# EMP2.net
KiCad netlist of a schematic drawn in EAGLE
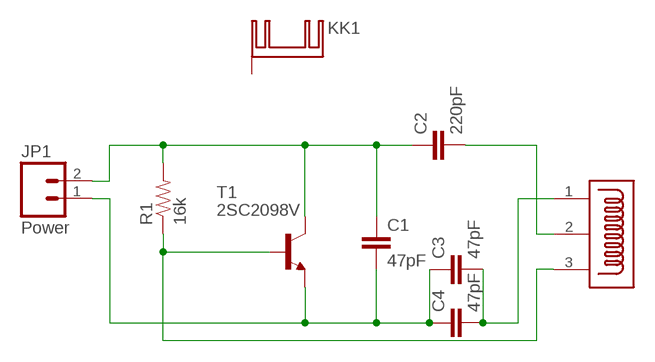
[diagram p0: schematic, sheet 1]

(export (version "E")
  (design (tool "Eeschema 10.0.6"))
  (components
    (comp (ref "C1")
      (value "47pF")
      (footprint "eagle-import:CAP-PTH-SMALL")
      (libsource (lib "eagle-import") (part "CAPPTH"))
    )
    (comp (ref "C2")
      (value "220pF")
      (footprint "eagle-import:CAP-PTH-SMALL")
      (libsource (lib "eagle-import") (part "CAPPTH"))
    )
    (comp (ref "C3")
      (value "47pF")
      (footprint "eagle-import:CAP-PTH-SMALL")
      (libsource (lib "eagle-import") (part "CAPPTH"))
    )
    (comp (ref "C4")
      (value "47pF")
      (footprint "eagle-import:CAP-PTH-SMALL")
      (libsource (lib "eagle-import") (part "CAPPTH"))
    )
    (comp (ref "JP1")
      (value "Power")
      (footprint "eagle-import:1X02")
      (libsource (lib "eagle-import") (part "M02PTH"))
    )
    (comp (ref "KK1")
      (value "D03PA-PAD")
      (footprint "eagle-import:D03PA-PAD")
      (libsource (lib "eagle-import") (part "D03PA-PAD"))
    )
    (comp (ref "R1")
      (value "16k")
      (footprint "eagle-import:AXIAL-0.5")
      (libsource (lib "eagle-import") (part "RESISTORPTH-1/2W"))
    )
    (comp (ref "T1")
      (value "2SC2098V")
      (footprint "eagle-import:TO220AV")
      (libsource (lib "eagle-import") (part "2SC2098V"))
    )
    (comp (ref "U$1")
      (value "EMP_WIRE")
      (footprint "eagle-import:EMP_WIRE")
      (libsource (lib "eagle-import") (part "EMP_WIRE"))
    )
  )
  (nets
    (net (code "1") (name "Net-(C2-Pad2)") (class "Default")
      (node (ref "C2") (pin "2") (pinfunction "2_2") (pintype "passive"))
      (node (ref "U$1") (pin "2") (pinfunction "2_2") (pintype "bidirectional"))
    )
    (net (code "2") (name "Net-(C3-Pad2)") (class "Default")
      (node (ref "C3") (pin "2") (pinfunction "2_2") (pintype "passive"))
      (node (ref "C4") (pin "2") (pinfunction "2_2") (pintype "passive"))
      (node (ref "U$1") (pin "1") (pinfunction "1_1") (pintype "bidirectional"))
    )
    (net (code "3") (name "Net-(R1-1)") (class "Default")
      (node (ref "R1") (pin "P$1") (pinfunction "1_P$1") (pintype "passive"))
      (node (ref "T1") (pin "1") (pinfunction "B_1") (pintype "passive"))
      (node (ref "U$1") (pin "3") (pinfunction "3_3") (pintype "bidirectional"))
    )
    (net (code "4") (name "Net-(R1-2)") (class "Default")
      (node (ref "C1") (pin "1") (pinfunction "1_1") (pintype "passive"))
      (node (ref "C2") (pin "1") (pinfunction "1_1") (pintype "passive"))
      (node (ref "JP1") (pin "2") (pinfunction "2_2") (pintype "passive"))
      (node (ref "R1") (pin "P$2") (pinfunction "2_P$2") (pintype "passive"))
      (node (ref "T1") (pin "2") (pinfunction "C_2") (pintype "passive"))
    )
    (net (code "5") (name "Net-(T1-E)") (class "Default")
      (node (ref "C1") (pin "2") (pinfunction "2_2") (pintype "passive"))
      (node (ref "C3") (pin "1") (pinfunction "1_1") (pintype "passive"))
      (node (ref "C4") (pin "1") (pinfunction "1_1") (pintype "passive"))
      (node (ref "JP1") (pin "1") (pinfunction "1_1") (pintype "passive"))
      (node (ref "T1") (pin "3") (pinfunction "E_3") (pintype "passive"))
    )
    (net (code "6") (name "unconnected-(KK1-K-PadB)") (class "Default")
      (node (ref "KK1") (pin "B") (pinfunction "K_B") (pintype "passive"))
    )
  )
)
